# pin.net
KiCad netlist of a schematic drawn in EAGLE
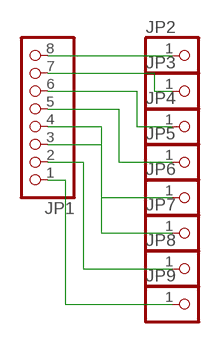
[diagram p0: schematic, sheet 1]

(export (version "E")
  (design (tool "Eeschema 10.0.6"))
  (components
    (comp (ref "JP1")
      (value "PINHD-1X8")
      (footprint "eagle-import:1X08")
      (libsource (lib "eagle-import") (part "PINHD-1X8"))
    )
    (comp (ref "JP2")
      (value "PINHD-1X1")
      (footprint "eagle-import:1X01")
      (libsource (lib "eagle-import") (part "PINHD-1X1"))
    )
    (comp (ref "JP3")
      (value "PINHD-1X1")
      (footprint "eagle-import:1X01")
      (libsource (lib "eagle-import") (part "PINHD-1X1"))
    )
    (comp (ref "JP4")
      (value "PINHD-1X1")
      (footprint "eagle-import:1X01")
      (libsource (lib "eagle-import") (part "PINHD-1X1"))
    )
    (comp (ref "JP5")
      (value "PINHD-1X1")
      (footprint "eagle-import:1X01")
      (libsource (lib "eagle-import") (part "PINHD-1X1"))
    )
    (comp (ref "JP6")
      (value "PINHD-1X1")
      (footprint "eagle-import:1X01")
      (libsource (lib "eagle-import") (part "PINHD-1X1"))
    )
    (comp (ref "JP7")
      (value "PINHD-1X1")
      (footprint "eagle-import:1X01")
      (libsource (lib "eagle-import") (part "PINHD-1X1"))
    )
    (comp (ref "JP8")
      (value "PINHD-1X1")
      (footprint "eagle-import:1X01")
      (libsource (lib "eagle-import") (part "PINHD-1X1"))
    )
    (comp (ref "JP9")
      (value "PINHD-1X1")
      (footprint "eagle-import:1X01")
      (libsource (lib "eagle-import") (part "PINHD-1X1"))
    )
  )
  (nets
    (net (code "1") (name "Net-(JP1-Pad1)") (class "Default")
      (node (ref "JP1") (pin "1") (pinfunction "1_1") (pintype "passive"))
      (node (ref "JP9") (pin "1") (pinfunction "1_1") (pintype "passive"))
    )
    (net (code "2") (name "Net-(JP1-Pad2)") (class "Default")
      (node (ref "JP1") (pin "2") (pinfunction "2_2") (pintype "passive"))
      (node (ref "JP8") (pin "1") (pinfunction "1_1") (pintype "passive"))
    )
    (net (code "3") (name "Net-(JP1-Pad3)") (class "Default")
      (node (ref "JP1") (pin "3") (pinfunction "3_3") (pintype "passive"))
      (node (ref "JP7") (pin "1") (pinfunction "1_1") (pintype "passive"))
    )
    (net (code "4") (name "Net-(JP1-Pad4)") (class "Default")
      (node (ref "JP1") (pin "4") (pinfunction "4_4") (pintype "passive"))
      (node (ref "JP6") (pin "1") (pinfunction "1_1") (pintype "passive"))
    )
    (net (code "5") (name "Net-(JP1-Pad5)") (class "Default")
      (node (ref "JP1") (pin "5") (pinfunction "5_5") (pintype "passive"))
      (node (ref "JP5") (pin "1") (pinfunction "1_1") (pintype "passive"))
    )
    (net (code "6") (name "Net-(JP1-Pad6)") (class "Default")
      (node (ref "JP1") (pin "6") (pinfunction "6_6") (pintype "passive"))
      (node (ref "JP4") (pin "1") (pinfunction "1_1") (pintype "passive"))
    )
    (net (code "7") (name "Net-(JP1-Pad7)") (class "Default")
      (node (ref "JP1") (pin "7") (pinfunction "7_7") (pintype "passive"))
      (node (ref "JP3") (pin "1") (pinfunction "1_1") (pintype "passive"))
    )
    (net (code "8") (name "Net-(JP1-Pad8)") (class "Default")
      (node (ref "JP1") (pin "8") (pinfunction "8_8") (pintype "passive"))
      (node (ref "JP2") (pin "1") (pinfunction "1_1") (pintype "passive"))
    )
  )
)
